# keyboard.net
KiCad netlist of a schematic drawn in EAGLE
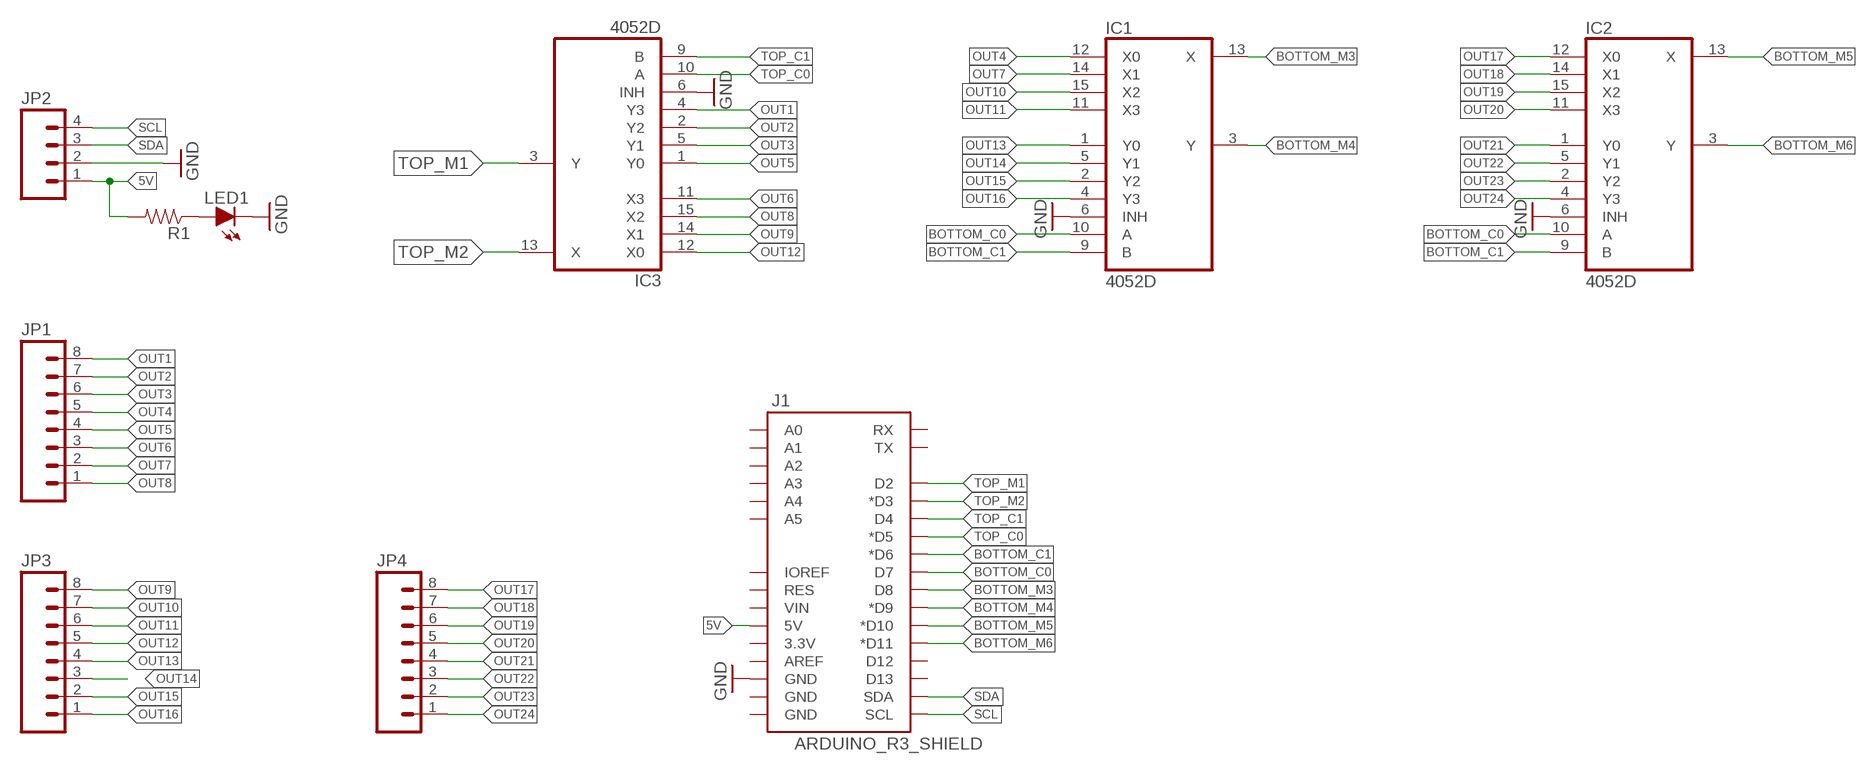
[diagram p0: schematic, sheet 1]

(export (version "E")
  (design (tool "Eeschema 10.0.6"))
  (components
    (comp (ref "IC1")
      (value "4052D")
      (footprint "eagle-import:SO16")
      (libsource (lib "eagle-import") (part "4052D"))
    )
    (comp (ref "IC2")
      (value "4052D")
      (footprint "eagle-import:SO16")
      (libsource (lib "eagle-import") (part "4052D"))
    )
    (comp (ref "IC3")
      (value "4052D")
      (footprint "eagle-import:SO16")
      (libsource (lib "eagle-import") (part "4052D"))
    )
    (comp (ref "J1")
      (value "ARDUINO_R3_SHIELD")
      (footprint "eagle-import:UNO_R3_SHIELD")
      (libsource (lib "eagle-import") (part "ARDUINO_R3_SHIELD"))
    )
    (comp (ref "JP1")
      (value "M08")
      (footprint "eagle-import:1X08")
      (libsource (lib "eagle-import") (part "M08"))
    )
    (comp (ref "JP2")
      (value "M04")
      (footprint "eagle-import:1X04")
      (libsource (lib "eagle-import") (part "M04"))
    )
    (comp (ref "JP3")
      (value "M08")
      (footprint "eagle-import:1X08")
      (libsource (lib "eagle-import") (part "M08"))
    )
    (comp (ref "JP4")
      (value "M08")
      (footprint "eagle-import:1X08")
      (libsource (lib "eagle-import") (part "M08"))
    )
    (comp (ref "LED1")
      (value "LED-5MM")
      (footprint "eagle-import:LED-5MM")
      (libsource (lib "eagle-import") (part "LED-5MM"))
    )
    (comp (ref "R1")
      (value "RESISTORPTH-1/2W")
      (footprint "eagle-import:AXIAL-0.5")
      (libsource (lib "eagle-import") (part "RESISTORPTH-1/2W"))
    )
  )
  (nets
    (net (code "1") (name "5V") (class "Default")
      (node (ref "J1") (pin "5V") (pinfunction "5V_5V") (pintype "bidirectional"))
      (node (ref "JP2") (pin "1") (pinfunction "1_1") (pintype "passive"))
      (node (ref "R1") (pin "P$2") (pinfunction "2_P$2") (pintype "passive"))
    )
    (net (code "2") (name "BOTTOM_C0") (class "Default")
      (node (ref "IC1") (pin "10") (pinfunction "A_10") (pintype "input"))
      (node (ref "IC2") (pin "10") (pinfunction "A_10") (pintype "input"))
      (node (ref "J1") (pin "D7") (pinfunction "D7_D7") (pintype "bidirectional"))
    )
    (net (code "3") (name "BOTTOM_C1") (class "Default")
      (node (ref "IC1") (pin "9") (pinfunction "B_9") (pintype "input"))
      (node (ref "IC2") (pin "9") (pinfunction "B_9") (pintype "input"))
      (node (ref "J1") (pin "D6") (pinfunction "*D6_D6") (pintype "bidirectional"))
    )
    (net (code "4") (name "BOTTOM_M3") (class "Default")
      (node (ref "IC1") (pin "13") (pinfunction "X_13") (pintype "bidirectional"))
      (node (ref "J1") (pin "D8") (pinfunction "D8_D8") (pintype "bidirectional"))
    )
    (net (code "5") (name "BOTTOM_M4") (class "Default")
      (node (ref "IC1") (pin "3") (pinfunction "Y_3") (pintype "bidirectional"))
      (node (ref "J1") (pin "D9") (pinfunction "*D9_D9") (pintype "bidirectional"))
    )
    (net (code "6") (name "BOTTOM_M5") (class "Default")
      (node (ref "IC2") (pin "13") (pinfunction "X_13") (pintype "bidirectional"))
      (node (ref "J1") (pin "D10") (pinfunction "*D10_D10") (pintype "bidirectional"))
    )
    (net (code "7") (name "BOTTOM_M6") (class "Default")
      (node (ref "IC2") (pin "3") (pinfunction "Y_3") (pintype "bidirectional"))
      (node (ref "J1") (pin "D11") (pinfunction "*D11_D11") (pintype "bidirectional"))
    )
    (net (code "8") (name "GND") (class "Default")
      (node (ref "IC1") (pin "6") (pinfunction "INH_6") (pintype "input"))
      (node (ref "IC2") (pin "6") (pinfunction "INH_6") (pintype "input"))
      (node (ref "IC3") (pin "6") (pinfunction "INH_6") (pintype "input"))
      (node (ref "J1") (pin "GND@2") (pinfunction "GND_GND@2") (pintype "bidirectional"))
      (node (ref "JP2") (pin "2") (pinfunction "2_2") (pintype "passive"))
      (node (ref "LED1") (pin "K") (pinfunction "C_K") (pintype "passive"))
    )
    (net (code "9") (name "Net-(R1-1)") (class "Default")
      (node (ref "LED1") (pin "A") (pinfunction "A_A") (pintype "passive"))
      (node (ref "R1") (pin "P$1") (pinfunction "1_P$1") (pintype "passive"))
    )
    (net (code "10") (name "OUT1") (class "Default")
      (node (ref "IC3") (pin "4") (pinfunction "Y3_4") (pintype "bidirectional"))
      (node (ref "JP1") (pin "8") (pinfunction "8_8") (pintype "passive"))
    )
    (net (code "11") (name "OUT2") (class "Default")
      (node (ref "IC3") (pin "2") (pinfunction "Y2_2") (pintype "bidirectional"))
      (node (ref "JP1") (pin "7") (pinfunction "7_7") (pintype "passive"))
    )
    (net (code "12") (name "OUT3") (class "Default")
      (node (ref "IC3") (pin "5") (pinfunction "Y1_5") (pintype "bidirectional"))
      (node (ref "JP1") (pin "6") (pinfunction "6_6") (pintype "passive"))
    )
    (net (code "13") (name "OUT4") (class "Default")
      (node (ref "IC1") (pin "12") (pinfunction "X0_12") (pintype "bidirectional"))
      (node (ref "JP1") (pin "5") (pinfunction "5_5") (pintype "passive"))
    )
    (net (code "14") (name "OUT5") (class "Default")
      (node (ref "IC3") (pin "1") (pinfunction "Y0_1") (pintype "bidirectional"))
      (node (ref "JP1") (pin "4") (pinfunction "4_4") (pintype "passive"))
    )
    (net (code "15") (name "OUT6") (class "Default")
      (node (ref "IC3") (pin "11") (pinfunction "X3_11") (pintype "bidirectional"))
      (node (ref "JP1") (pin "3") (pinfunction "3_3") (pintype "passive"))
    )
    (net (code "16") (name "OUT7") (class "Default")
      (node (ref "IC1") (pin "14") (pinfunction "X1_14") (pintype "bidirectional"))
      (node (ref "JP1") (pin "2") (pinfunction "2_2") (pintype "passive"))
    )
    (net (code "17") (name "OUT8") (class "Default")
      (node (ref "IC3") (pin "15") (pinfunction "X2_15") (pintype "bidirectional"))
      (node (ref "JP1") (pin "1") (pinfunction "1_1") (pintype "passive"))
    )
    (net (code "18") (name "OUT9") (class "Default")
      (node (ref "IC3") (pin "14") (pinfunction "X1_14") (pintype "bidirectional"))
      (node (ref "JP3") (pin "8") (pinfunction "8_8") (pintype "passive"))
    )
    (net (code "19") (name "OUT10") (class "Default")
      (node (ref "IC1") (pin "15") (pinfunction "X2_15") (pintype "bidirectional"))
      (node (ref "JP3") (pin "7") (pinfunction "7_7") (pintype "passive"))
    )
    (net (code "20") (name "OUT11") (class "Default")
      (node (ref "IC1") (pin "11") (pinfunction "X3_11") (pintype "bidirectional"))
      (node (ref "JP3") (pin "6") (pinfunction "6_6") (pintype "passive"))
    )
    (net (code "21") (name "OUT12") (class "Default")
      (node (ref "IC3") (pin "12") (pinfunction "X0_12") (pintype "bidirectional"))
      (node (ref "JP3") (pin "5") (pinfunction "5_5") (pintype "passive"))
    )
    (net (code "22") (name "OUT13") (class "Default")
      (node (ref "IC1") (pin "1") (pinfunction "Y0_1") (pintype "bidirectional"))
      (node (ref "JP3") (pin "4") (pinfunction "4_4") (pintype "passive"))
    )
    (net (code "23") (name "OUT14") (class "Default")
      (node (ref "IC1") (pin "5") (pinfunction "Y1_5") (pintype "bidirectional"))
      (node (ref "JP3") (pin "3") (pinfunction "3_3") (pintype "passive"))
    )
    (net (code "24") (name "OUT15") (class "Default")
      (node (ref "IC1") (pin "2") (pinfunction "Y2_2") (pintype "bidirectional"))
      (node (ref "JP3") (pin "2") (pinfunction "2_2") (pintype "passive"))
    )
    (net (code "25") (name "OUT16") (class "Default")
      (node (ref "IC1") (pin "4") (pinfunction "Y3_4") (pintype "bidirectional"))
      (node (ref "JP3") (pin "1") (pinfunction "1_1") (pintype "passive"))
    )
    (net (code "26") (name "OUT17") (class "Default")
      (node (ref "IC2") (pin "12") (pinfunction "X0_12") (pintype "bidirectional"))
      (node (ref "JP4") (pin "8") (pinfunction "8_8") (pintype "passive"))
    )
    (net (code "27") (name "OUT18") (class "Default")
      (node (ref "IC2") (pin "14") (pinfunction "X1_14") (pintype "bidirectional"))
      (node (ref "JP4") (pin "7") (pinfunction "7_7") (pintype "passive"))
    )
    (net (code "28") (name "OUT19") (class "Default")
      (node (ref "IC2") (pin "15") (pinfunction "X2_15") (pintype "bidirectional"))
      (node (ref "JP4") (pin "6") (pinfunction "6_6") (pintype "passive"))
    )
    (net (code "29") (name "OUT20") (class "Default")
      (node (ref "IC2") (pin "11") (pinfunction "X3_11") (pintype "bidirectional"))
      (node (ref "JP4") (pin "5") (pinfunction "5_5") (pintype "passive"))
    )
    (net (code "30") (name "OUT21") (class "Default")
      (node (ref "IC2") (pin "1") (pinfunction "Y0_1") (pintype "bidirectional"))
      (node (ref "JP4") (pin "4") (pinfunction "4_4") (pintype "passive"))
    )
    (net (code "31") (name "OUT22") (class "Default")
      (node (ref "IC2") (pin "5") (pinfunction "Y1_5") (pintype "bidirectional"))
      (node (ref "JP4") (pin "3") (pinfunction "3_3") (pintype "passive"))
    )
    (net (code "32") (name "OUT23") (class "Default")
      (node (ref "IC2") (pin "2") (pinfunction "Y2_2") (pintype "bidirectional"))
      (node (ref "JP4") (pin "2") (pinfunction "2_2") (pintype "passive"))
    )
    (net (code "33") (name "OUT24") (class "Default")
      (node (ref "IC2") (pin "4") (pinfunction "Y3_4") (pintype "bidirectional"))
      (node (ref "JP4") (pin "1") (pinfunction "1_1") (pintype "passive"))
    )
    (net (code "34") (name "SCL") (class "Default")
      (node (ref "J1") (pin "SCL") (pinfunction "SCL_SCL") (pintype "bidirectional"))
      (node (ref "JP2") (pin "4") (pinfunction "4_4") (pintype "passive"))
    )
    (net (code "35") (name "SDA") (class "Default")
      (node (ref "J1") (pin "SDA") (pinfunction "SDA_SDA") (pintype "bidirectional"))
      (node (ref "JP2") (pin "3") (pinfunction "3_3") (pintype "passive"))
    )
    (net (code "36") (name "TOP_C0") (class "Default")
      (node (ref "IC3") (pin "10") (pinfunction "A_10") (pintype "input"))
      (node (ref "J1") (pin "D5") (pinfunction "*D5_D5") (pintype "bidirectional"))
    )
    (net (code "37") (name "TOP_C1") (class "Default")
      (node (ref "IC3") (pin "9") (pinfunction "B_9") (pintype "input"))
      (node (ref "J1") (pin "D4") (pinfunction "D4_D4") (pintype "bidirectional"))
    )
    (net (code "38") (name "TOP_M1") (class "Default")
      (node (ref "IC3") (pin "3") (pinfunction "Y_3") (pintype "bidirectional"))
      (node (ref "J1") (pin "D2") (pinfunction "D2_D2") (pintype "bidirectional"))
    )
    (net (code "39") (name "TOP_M2") (class "Default")
      (node (ref "IC3") (pin "13") (pinfunction "X_13") (pintype "bidirectional"))
      (node (ref "J1") (pin "D3") (pinfunction "*D3_D3") (pintype "bidirectional"))
    )
    (net (code "40") (name "unconnected-(J1-GND-PadGND@0)") (class "Default")
      (node (ref "J1") (pin "GND@0") (pinfunction "GND_GND@0") (pintype "bidirectional"))
    )
    (net (code "41") (name "unconnected-(J1-GND-PadGND@1)") (class "Default")
      (node (ref "J1") (pin "GND@1") (pinfunction "GND_GND@1") (pintype "bidirectional"))
    )
    (net (code "42") (name "unconnected-(J1-Pad3.3V)") (class "Default")
      (node (ref "J1") (pin "3.3V") (pinfunction "3.3V_3.3V") (pintype "bidirectional"))
    )
    (net (code "43") (name "unconnected-(J1-PadA0)") (class "Default")
      (node (ref "J1") (pin "A0") (pinfunction "A0_A0") (pintype "bidirectional"))
    )
    (net (code "44") (name "unconnected-(J1-PadA1)") (class "Default")
      (node (ref "J1") (pin "A1") (pinfunction "A1_A1") (pintype "bidirectional"))
    )
    (net (code "45") (name "unconnected-(J1-PadA2)") (class "Default")
      (node (ref "J1") (pin "A2") (pinfunction "A2_A2") (pintype "bidirectional"))
    )
    (net (code "46") (name "unconnected-(J1-PadA3)") (class "Default")
      (node (ref "J1") (pin "A3") (pinfunction "A3_A3") (pintype "bidirectional"))
    )
    (net (code "47") (name "unconnected-(J1-PadA4)") (class "Default")
      (node (ref "J1") (pin "A4") (pinfunction "A4_A4") (pintype "bidirectional"))
    )
    (net (code "48") (name "unconnected-(J1-PadA5)") (class "Default")
      (node (ref "J1") (pin "A5") (pinfunction "A5_A5") (pintype "bidirectional"))
    )
    (net (code "49") (name "unconnected-(J1-PadAREF)") (class "Default")
      (node (ref "J1") (pin "AREF") (pinfunction "AREF_AREF") (pintype "bidirectional"))
    )
    (net (code "50") (name "unconnected-(J1-PadD12)") (class "Default")
      (node (ref "J1") (pin "D12") (pinfunction "D12_D12") (pintype "bidirectional"))
    )
    (net (code "51") (name "unconnected-(J1-PadD13)") (class "Default")
      (node (ref "J1") (pin "D13") (pinfunction "D13_D13") (pintype "bidirectional"))
    )
    (net (code "52") (name "unconnected-(J1-PadIOREF)") (class "Default")
      (node (ref "J1") (pin "IOREF") (pinfunction "IOREF_IOREF") (pintype "bidirectional"))
    )
    (net (code "53") (name "unconnected-(J1-PadRES)") (class "Default")
      (node (ref "J1") (pin "RES") (pinfunction "RES_RES") (pintype "bidirectional"))
    )
    (net (code "54") (name "unconnected-(J1-PadRX)") (class "Default")
      (node (ref "J1") (pin "RX") (pinfunction "RX_RX") (pintype "bidirectional"))
    )
    (net (code "55") (name "unconnected-(J1-PadTX)") (class "Default")
      (node (ref "J1") (pin "TX") (pinfunction "TX_TX") (pintype "bidirectional"))
    )
    (net (code "56") (name "unconnected-(J1-PadVIN)") (class "Default")
      (node (ref "J1") (pin "VIN") (pinfunction "VIN_VIN") (pintype "bidirectional"))
    )
  )
)
